# prop-driver.net
KiCad netlist of a schematic drawn in EAGLE
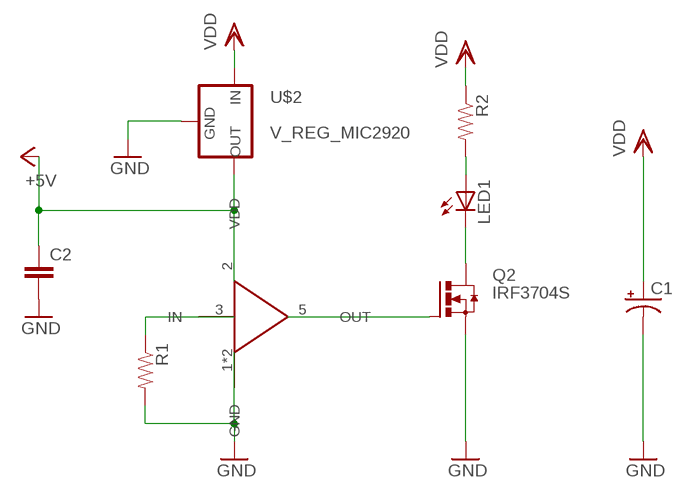
[diagram p0: schematic, sheet 1]

(export (version "E")
  (design (tool "Eeschema 10.0.6"))
  (components
    (comp (ref "C1")
      (value "CAP_POLD")
      (footprint "eagle-import:PANASONIC_D")
      (libsource (lib "eagle-import") (part "CAP_POLD"))
    )
    (comp (ref "C2")
      (value "CAP1206")
      (footprint "eagle-import:1206")
      (libsource (lib "eagle-import") (part "CAP1206"))
    )
    (comp (ref "LED1")
      (value "LED-FKIT-1206")
      (footprint "eagle-import:FKIT-LED-1206")
      (libsource (lib "eagle-import") (part "LED-FKIT-1206"))
    )
    (comp (ref "Q2")
      (value "IRF3704S")
      (footprint "eagle-import:D2PACK")
      (libsource (lib "eagle-import") (part "IRF3704S"))
    )
    (comp (ref "R1")
      (value "RESISTOR1206")
      (footprint "eagle-import:1206")
      (libsource (lib "eagle-import") (part "RESISTOR1206"))
    )
    (comp (ref "R2")
      (value "RESISTOR1206")
      (footprint "eagle-import:1206")
      (libsource (lib "eagle-import") (part "RESISTOR1206"))
    )
    (comp (ref "U$1")
      (value "MCP1402")
      (footprint "eagle-import:SOT23-5")
      (libsource (lib "eagle-import") (part "MCP1402"))
    )
    (comp (ref "U$2")
      (value "V_REG_MIC2920")
      (footprint "eagle-import:SOT223")
      (libsource (lib "eagle-import") (part "V_REG_MIC2920"))
    )
  )
  (nets
    (net (code "1") (name "+5V") (class "Default")
      (node (ref "C2") (pin "1") (pinfunction "1_1") (pintype "passive"))
      (node (ref "U$1") (pin "2") (pinfunction "VDD_2") (pintype "bidirectional"))
      (node (ref "U$2") (pin "3") (pinfunction "OUT_3") (pintype "output"))
    )
    (net (code "2") (name "GND") (class "Default")
      (node (ref "C1") (pin "-") (pinfunction "-_-") (pintype "passive"))
      (node (ref "C2") (pin "2") (pinfunction "2_2") (pintype "passive"))
      (node (ref "Q2") (pin "3") (pinfunction "S_3") (pintype "passive"))
      (node (ref "R1") (pin "2") (pinfunction "2_2") (pintype "passive"))
      (node (ref "U$1") (pin "1") (pinfunction "GND_1") (pintype "bidirectional"))
      (node (ref "U$1") (pin "4") (pinfunction "GND_4") (pintype "bidirectional"))
      (node (ref "U$2") (pin "2") (pinfunction "GND_2") (pintype "input"))
    )
    (net (code "3") (name "Net-(LED1-PadA)") (class "Default")
      (node (ref "LED1") (pin "A") (pinfunction "A_A") (pintype "passive"))
      (node (ref "R2") (pin "2") (pinfunction "2_2") (pintype "passive"))
    )
    (net (code "4") (name "Net-(Q2-D)") (class "Default")
      (node (ref "LED1") (pin "C") (pinfunction "C_C") (pintype "passive"))
      (node (ref "Q2") (pin "2") (pinfunction "D_2") (pintype "passive"))
    )
    (net (code "5") (name "Net-(Q2-G)") (class "Default")
      (node (ref "Q2") (pin "1") (pinfunction "G_1") (pintype "passive"))
      (node (ref "U$1") (pin "5") (pinfunction "OUT_5") (pintype "bidirectional"))
    )
    (net (code "6") (name "Net-(U$1-IN)") (class "Default")
      (node (ref "R1") (pin "1") (pinfunction "1_1") (pintype "passive"))
      (node (ref "U$1") (pin "3") (pinfunction "IN_3") (pintype "bidirectional"))
    )
    (net (code "7") (name "VDD") (class "Default")
      (node (ref "C1") (pin "+") (pinfunction "+_+") (pintype "passive"))
      (node (ref "R2") (pin "1") (pinfunction "1_1") (pintype "passive"))
      (node (ref "U$2") (pin "1") (pinfunction "IN_1") (pintype "input"))
    )
  )
)
